# HMMOD-UART-CP2102-USB-V01-002.net
KiCad netlist of a schematic drawn in EAGLE
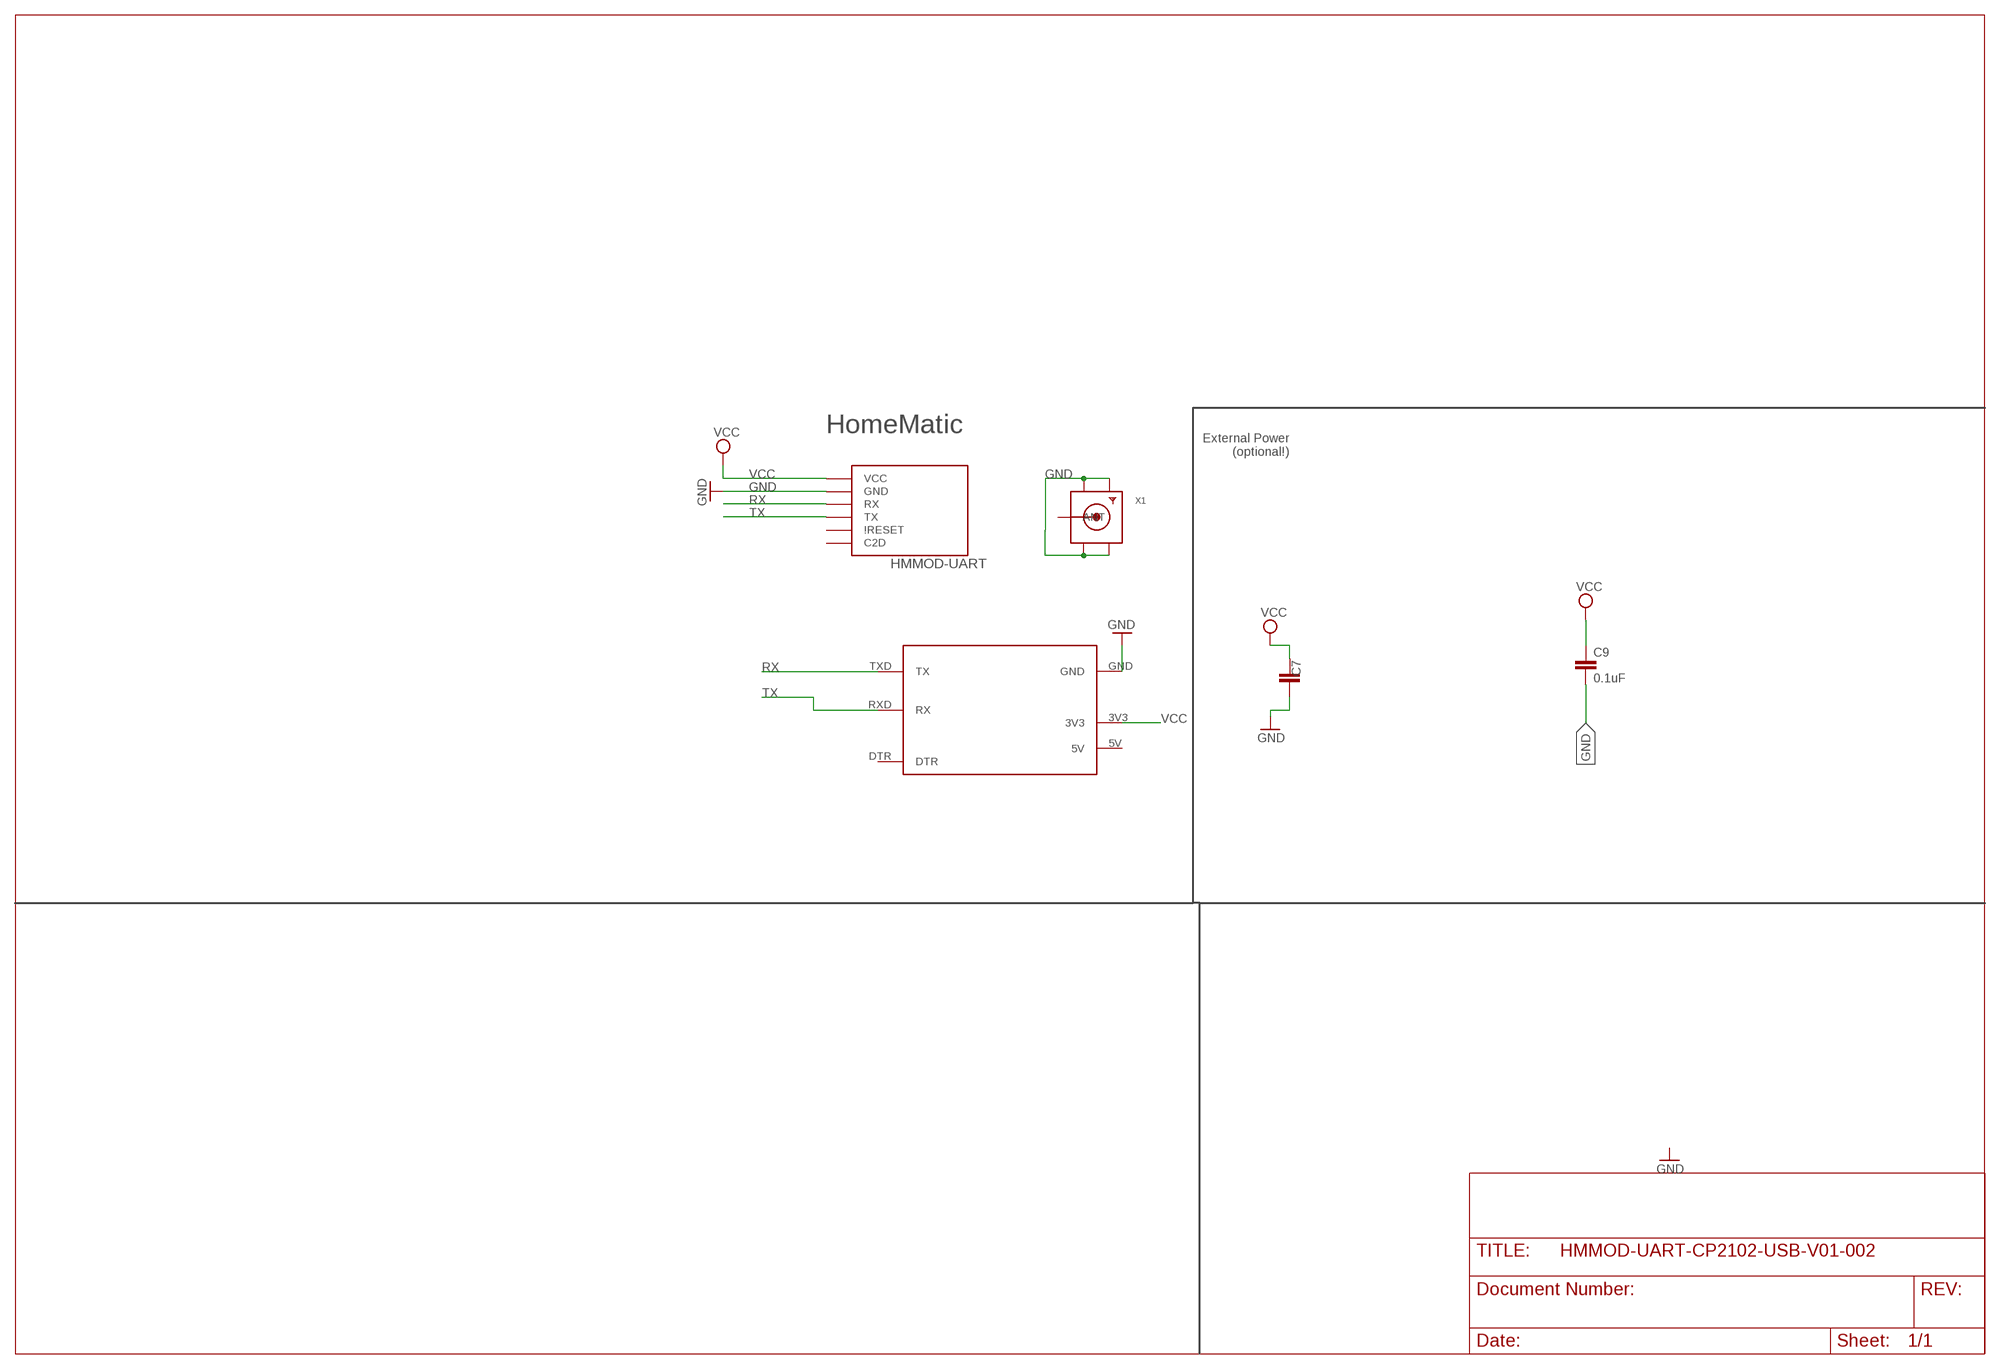
[diagram p0: schematic, sheet 1]

(export (version "E")
  (design (tool "Eeschema 10.0.6"))
  (components
    (comp (ref "C7")
      (value "C-EUC1812")
      (footprint "eagle-import:C1812")
      (libsource (lib "eagle-import") (part "C-EUC1812"))
    )
    (comp (ref "C9")
      (value "0.1uF")
      (footprint "eagle-import:C0805")
      (libsource (lib "eagle-import") (part "C-EUC0805"))
    )
    (comp (ref "HMMOD-UART")
      (value "HM-MOD-UARTDIL")
      (footprint "eagle-import:HM-MOD-UART-DIL")
      (libsource (lib "eagle-import") (part "HM-MOD-UARTDIL"))
    )
    (comp (ref "U$1")
      (value "CP2101")
      (footprint "eagle-import:CP2101-BEAKOUT")
      (libsource (lib "eagle-import") (part "CP2101"))
    )
    (comp (ref "X1")
      (value "SMACONNECTOR_EDGE")
      (footprint "eagle-import:SMA_EDGELAUNCH")
      (libsource (lib "eagle-import") (part "SMACONNECTOR_EDGE"))
    )
  )
  (nets
    (net (code "1") (name "/5V") (class "Default")
      (node (ref "U$1") (pin "5V") (pinfunction "5V_5V") (pintype "power_in"))
    )
    (net (code "2") (name "/RX") (class "Default")
      (node (ref "HMMOD-UART") (pin "6") (pinfunction "RX_6") (pintype "bidirectional"))
      (node (ref "U$1") (pin "TXD") (pinfunction "TX_TXD") (pintype "output"))
    )
    (net (code "3") (name "/TX") (class "Default")
      (node (ref "HMMOD-UART") (pin "5") (pinfunction "TX_5") (pintype "bidirectional"))
      (node (ref "U$1") (pin "RXD") (pinfunction "RX_RXD") (pintype "input"))
    )
    (net (code "4") (name "GND") (class "Default")
      (node (ref "C7") (pin "1") (pinfunction "1_1") (pintype "passive"))
      (node (ref "C9") (pin "2") (pinfunction "2_2") (pintype "passive"))
      (node (ref "HMMOD-UART") (pin "2") (pinfunction "GND_2") (pintype "power_in"))
      (node (ref "U$1") (pin "GND") (pinfunction "GND_GND") (pintype "power_in"))
      (node (ref "X1") (pin "GND@1") (pinfunction "GND4_GND@1") (pintype "power_in"))
      (node (ref "X1") (pin "GND@2") (pinfunction "GND3_GND@2") (pintype "power_in"))
      (node (ref "X1") (pin "GND@3") (pinfunction "GND2_GND@3") (pintype "power_in"))
      (node (ref "X1") (pin "GND@4") (pinfunction "GND1_GND@4") (pintype "power_in"))
    )
    (net (code "5") (name "VCC") (class "Default")
      (node (ref "C7") (pin "2") (pinfunction "2_2") (pintype "passive"))
      (node (ref "C9") (pin "1") (pinfunction "1_1") (pintype "passive"))
      (node (ref "HMMOD-UART") (pin "1") (pinfunction "VCC_1") (pintype "power_in"))
      (node (ref "U$1") (pin "3V3") (pinfunction "3V3_3V3") (pintype "power_in"))
    )
    (net (code "6") (name "unconnected-(HMMOD-UART-C2D-Pad3)") (class "Default")
      (node (ref "HMMOD-UART") (pin "3") (pinfunction "C2D_3") (pintype "bidirectional"))
    )
    (net (code "7") (name "unconnected-(HMMOD-UART-\\~{RESET}-Pad4)") (class "Default")
      (node (ref "HMMOD-UART") (pin "4") (pinfunction "\\~{RESET}_4") (pintype "bidirectional"))
    )
    (net (code "8") (name "unconnected-(U$1-PadDTR)") (class "Default")
      (node (ref "U$1") (pin "DTR") (pinfunction "DTR_DTR") (pintype "bidirectional"))
    )
    (net (code "9") (name "unconnected-(X1-ANT-PadP)") (class "Default")
      (node (ref "X1") (pin "P") (pinfunction "ANT_P") (pintype "bidirectional"))
    )
  )
)
